# FreqRef.net
KiCad netlist of a schematic drawn in EAGLE
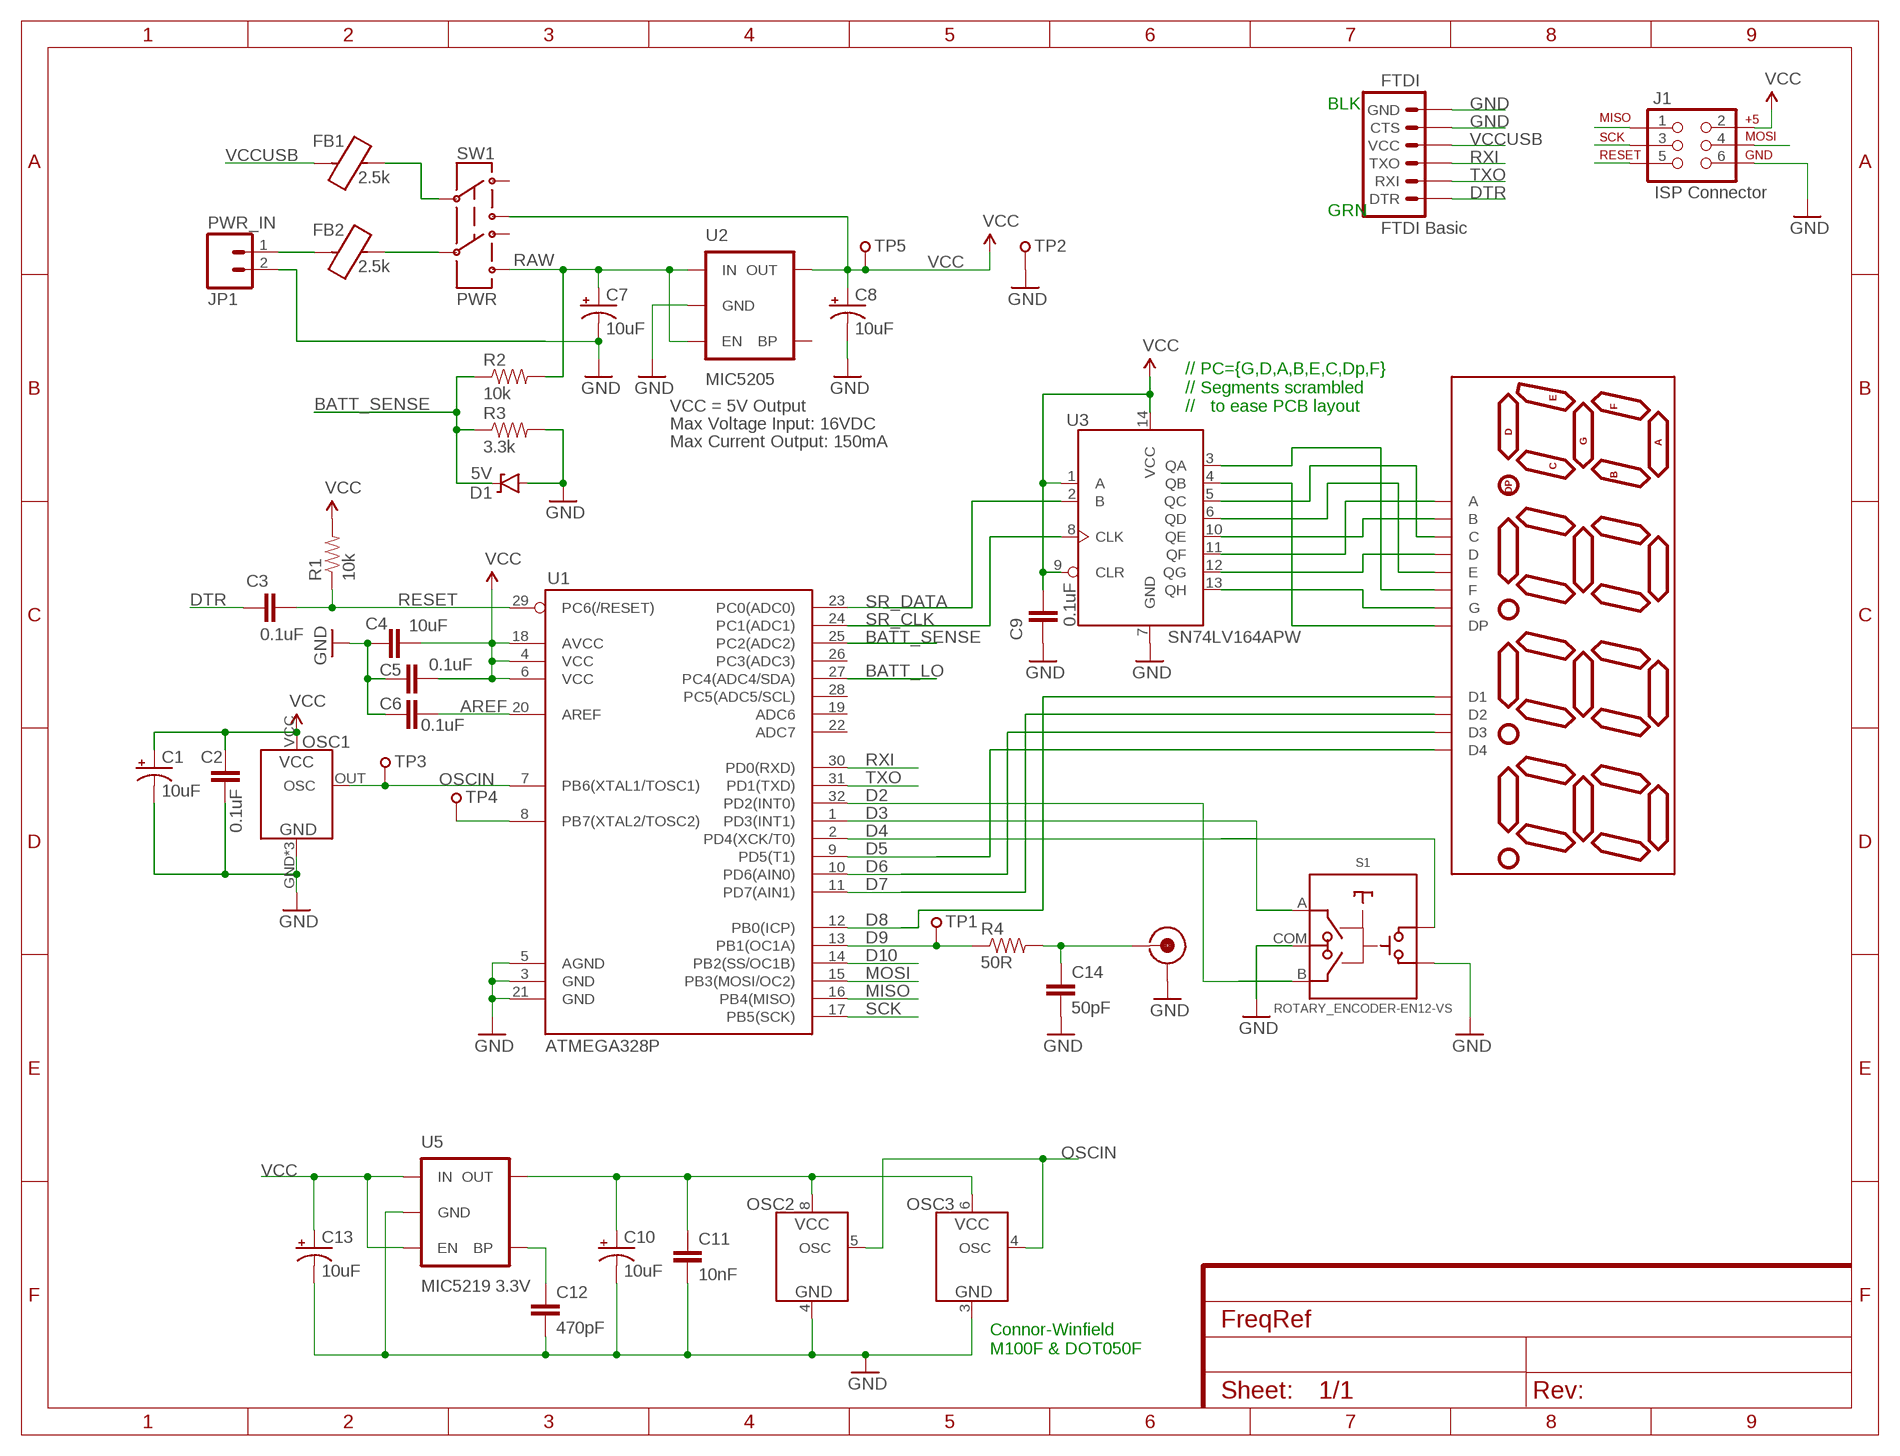
[diagram p0: schematic, sheet 1]

(export (version "E")
  (design (tool "Eeschema 10.0.6"))
  (components
    (comp (ref "C1")
      (value "10uF")
      (footprint "eagle-import:0805-POL")
      (libsource (lib "eagle-import") (part "CAP_POL0805"))
    )
    (comp (ref "C2")
      (value "0.1uF")
      (footprint "eagle-import:0805")
      (libsource (lib "eagle-import") (part "CAP0805"))
    )
    (comp (ref "C3")
      (value "0.1uF")
      (footprint "eagle-import:0805")
      (libsource (lib "eagle-import") (part "CAP0805"))
    )
    (comp (ref "C4")
      (value "10uF")
      (footprint "eagle-import:0805")
      (libsource (lib "eagle-import") (part "CAP0805"))
    )
    (comp (ref "C5")
      (value "0.1uF")
      (footprint "eagle-import:0805")
      (libsource (lib "eagle-import") (part "CAP0805"))
    )
    (comp (ref "C6")
      (value "0.1uF")
      (footprint "eagle-import:0805")
      (libsource (lib "eagle-import") (part "CAP0805"))
    )
    (comp (ref "C7")
      (value "10uF")
      (footprint "eagle-import:0805-POL")
      (libsource (lib "eagle-import") (part "CAP_POL0805"))
    )
    (comp (ref "C8")
      (value "10uF")
      (footprint "eagle-import:0805-POL")
      (libsource (lib "eagle-import") (part "CAP_POL0805"))
    )
    (comp (ref "C9")
      (value "0.1uF")
      (footprint "eagle-import:0805")
      (libsource (lib "eagle-import") (part "CAP0805"))
    )
    (comp (ref "C10")
      (value "10uF")
      (footprint "eagle-import:0805-POL")
      (libsource (lib "eagle-import") (part "CAP_POL0805"))
    )
    (comp (ref "C11")
      (value "10nF")
      (footprint "eagle-import:0805")
      (libsource (lib "eagle-import") (part "CAP0805"))
    )
    (comp (ref "C12")
      (value "470pF")
      (footprint "eagle-import:0805")
      (libsource (lib "eagle-import") (part "CAP0805"))
    )
    (comp (ref "C13")
      (value "10uF")
      (footprint "eagle-import:0805-POL")
      (libsource (lib "eagle-import") (part "CAP_POL0805"))
    )
    (comp (ref "C14")
      (value "50pF")
      (footprint "eagle-import:0805")
      (libsource (lib "eagle-import") (part "CAP0805"))
    )
    (comp (ref "D1")
      (value "5V")
      (footprint "eagle-import:SOD-323")
      (libsource (lib "eagle-import") (part "DIODE-ZENER3.3V"))
    )
    (comp (ref "DISP1")
      (value "HP_DISPLAY")
      (footprint "eagle-import:DIL12")
      (libsource (lib "eagle-import") (part "HP_DISPLAY"))
    )
    (comp (ref "FB1")
      (value "2.5k")
      (footprint "eagle-import:0805")
      (libsource (lib "eagle-import") (part "FERRITE_BEAD_0805"))
    )
    (comp (ref "FB2")
      (value "2.5k")
      (footprint "eagle-import:0805")
      (libsource (lib "eagle-import") (part "FERRITE_BEAD_0805"))
    )
    (comp (ref "FRAME1")
      (value "FRAME_LTR_CU_MARK")
      (footprint "eagle-import:FR-LTR-ON-PCB")
      (fields
        (field (name "CNAME") "Frequency Reference")
        (field (name "CREVISION") "Rev-B")
        (field (name "DESIGNER") "C.Schnarel")
      )
      (libsource (lib "eagle-import") (part "FRAME_LTR_CU_MARK"))
    )
    (comp (ref "FTDI")
      (value "FTDI Basic")
      (footprint "eagle-import:1X06")
      (libsource (lib "eagle-import") (part "ARDUINO_SERIAL_PROGRAMPTH"))
    )
    (comp (ref "J1")
      (value "ISP Connector")
      (footprint "eagle-import:2X3")
      (libsource (lib "eagle-import") (part "AVR_SPI_PRG_6PTH"))
    )
    (comp (ref "J2")
      (value "BNC_RIGHT-ANGLE")
      (footprint "eagle-import:BNC-RIGHT-ANGLE")
      (libsource (lib "eagle-import") (part "BNC_RIGHT-ANGLE"))
    )
    (comp (ref "JP1")
      (value "PWR_IN")
      (footprint "eagle-import:MOLEX-1X2")
      (libsource (lib "eagle-import") (part "M02POLAR"))
    )
    (comp (ref "OSC1")
      (value "TCXORALTRON")
      (footprint "eagle-import:TCXO")
      (libsource (lib "eagle-import") (part "TCXORALTRON"))
    )
    (comp (ref "OSC2")
      (value "TCXOM100")
      (footprint "eagle-import:TCXO-3.2X5")
      (libsource (lib "eagle-import") (part "TCXOM100"))
    )
    (comp (ref "OSC3")
      (value "TCXODOT")
      (footprint "eagle-import:TCXO-9X14")
      (libsource (lib "eagle-import") (part "TCXODOT"))
    )
    (comp (ref "R1")
      (value "10k")
      (footprint "eagle-import:0805")
      (libsource (lib "eagle-import") (part "RESISTOR0805-RES"))
    )
    (comp (ref "R2")
      (value "10k")
      (footprint "eagle-import:0805")
      (libsource (lib "eagle-import") (part "RESISTOR0805-RES"))
    )
    (comp (ref "R3")
      (value "3.3k")
      (footprint "eagle-import:0805")
      (libsource (lib "eagle-import") (part "RESISTOR0805-RES"))
    )
    (comp (ref "R4")
      (value "50R")
      (footprint "eagle-import:0805")
      (libsource (lib "eagle-import") (part "RESISTOR0805-RES"))
    )
    (comp (ref "S1")
      (value "ROTARY_ENCODER-EN12-VS")
      (footprint "eagle-import:EN12-VS")
      (libsource (lib "eagle-import") (part "ROTARY_ENCODER-EN12-VS"))
    )
    (comp (ref "SW1")
      (value "PWR")
      (footprint "eagle-import:8X10_BUTTON_ROUND")
      (libsource (lib "eagle-import") (part "SWITCH,BUTTON,ROUND,7MM"))
    )
    (comp (ref "TP1")
      (value "TEST_POINT")
      (footprint "eagle-import:BBD-VIA")
      (libsource (lib "eagle-import") (part "TEST_POINT"))
    )
    (comp (ref "TP2")
      (value "TEST_POINT")
      (footprint "eagle-import:BBD-VIA")
      (libsource (lib "eagle-import") (part "TEST_POINT"))
    )
    (comp (ref "TP3")
      (value "TEST_POINT")
      (footprint "eagle-import:BBD-VIA")
      (libsource (lib "eagle-import") (part "TEST_POINT"))
    )
    (comp (ref "TP4")
      (value "TEST_POINT")
      (footprint "eagle-import:BBD-VIA")
      (libsource (lib "eagle-import") (part "TEST_POINT"))
    )
    (comp (ref "TP5")
      (value "TEST_POINT")
      (footprint "eagle-import:BBD-VIA")
      (libsource (lib "eagle-import") (part "TEST_POINT"))
    )
    (comp (ref "U1")
      (value "ATMEGA328P")
      (footprint "eagle-import:TQFP32-08")
      (libsource (lib "eagle-import") (part "ATMEGA168"))
    )
    (comp (ref "U2")
      (value "MIC5205")
      (footprint "eagle-import:SOT23-5")
      (libsource (lib "eagle-import") (part "V_REG_LDOSMD"))
    )
    (comp (ref "U3")
      (value "SN74LV164APW")
      (footprint "eagle-import:TSSOP-14(TI)")
      (libsource (lib "eagle-import") (part "SN74LV164APW"))
    )
    (comp (ref "U5")
      (value "MIC5219 3.3V")
      (footprint "eagle-import:SOT23-5")
      (libsource (lib "eagle-import") (part "V_REG_MIC52193.3V"))
    )
  )
  (nets
    (net (code "1") (name "/AREF") (class "Default")
      (node (ref "C6") (pin "2") (pinfunction "2_2") (pintype "passive"))
      (node (ref "U1") (pin "20") (pinfunction "AREF_20") (pintype "bidirectional"))
    )
    (net (code "2") (name "/BATT_LO") (class "Default")
      (node (ref "U1") (pin "27") (pinfunction "PC4(ADC4/SDA)_27") (pintype "bidirectional"))
    )
    (net (code "3") (name "/BATT_SENSE") (class "Default")
      (node (ref "D1") (pin "C") (pinfunction "C_C") (pintype "passive"))
      (node (ref "R2") (pin "1") (pinfunction "1_1") (pintype "passive"))
      (node (ref "R3") (pin "1") (pinfunction "1_1") (pintype "passive"))
      (node (ref "U1") (pin "25") (pinfunction "PC2(ADC2)_25") (pintype "bidirectional"))
    )
    (net (code "4") (name "/D2") (class "Default")
      (node (ref "S1") (pin "B") (pinfunction "B_B") (pintype "bidirectional"))
      (node (ref "U1") (pin "32") (pinfunction "PD2(INT0)_32") (pintype "bidirectional"))
    )
    (net (code "5") (name "/D3") (class "Default")
      (node (ref "S1") (pin "A") (pinfunction "A_A") (pintype "bidirectional"))
      (node (ref "U1") (pin "1") (pinfunction "PD3(INT1)_1") (pintype "bidirectional"))
    )
    (net (code "6") (name "/D4") (class "Default")
      (node (ref "S1") (pin "D") (pinfunction "P$4_D") (pintype "bidirectional"))
      (node (ref "U1") (pin "2") (pinfunction "PD4(XCK/T0)_2") (pintype "bidirectional"))
    )
    (net (code "7") (name "/D5") (class "Default")
      (node (ref "DISP1") (pin "6") (pinfunction "D4_6") (pintype "bidirectional"))
      (node (ref "U1") (pin "9") (pinfunction "PD5(T1)_9") (pintype "bidirectional"))
    )
    (net (code "8") (name "/D6") (class "Default")
      (node (ref "DISP1") (pin "4") (pinfunction "D3_4") (pintype "bidirectional"))
      (node (ref "U1") (pin "10") (pinfunction "PD6(AIN0)_10") (pintype "bidirectional"))
    )
    (net (code "9") (name "/D7") (class "Default")
      (node (ref "DISP1") (pin "10") (pinfunction "D2_10") (pintype "bidirectional"))
      (node (ref "U1") (pin "11") (pinfunction "PD7(AIN1)_11") (pintype "bidirectional"))
    )
    (net (code "10") (name "/D8") (class "Default")
      (node (ref "DISP1") (pin "1") (pinfunction "D1_1") (pintype "bidirectional"))
      (node (ref "U1") (pin "12") (pinfunction "PB0(ICP)_12") (pintype "bidirectional"))
    )
    (net (code "11") (name "/D9") (class "Default")
      (node (ref "R4") (pin "1") (pinfunction "1_1") (pintype "passive"))
      (node (ref "TP1") (pin "P$1") (pinfunction "P$1_P$1") (pintype "bidirectional"))
      (node (ref "U1") (pin "13") (pinfunction "PB1(OC1A)_13") (pintype "bidirectional"))
    )
    (net (code "12") (name "/D10") (class "Default")
      (node (ref "U1") (pin "14") (pinfunction "PB2(SS/OC1B)_14") (pintype "bidirectional"))
    )
    (net (code "13") (name "/DTR") (class "Default")
      (node (ref "C3") (pin "1") (pinfunction "1_1") (pintype "passive"))
      (node (ref "FTDI") (pin "1") (pinfunction "DTR_1") (pintype "passive"))
    )
    (net (code "14") (name "/MISO") (class "Default")
      (node (ref "J1") (pin "1") (pinfunction "1_1") (pintype "passive"))
      (node (ref "U1") (pin "16") (pinfunction "PB4(MISO)_16") (pintype "bidirectional"))
    )
    (net (code "15") (name "/MOSI") (class "Default")
      (node (ref "J1") (pin "4") (pinfunction "4_4") (pintype "passive"))
      (node (ref "U1") (pin "15") (pinfunction "PB3(MOSI/OC2)_15") (pintype "bidirectional"))
    )
    (net (code "16") (name "/OSCIN") (class "Default")
      (node (ref "OSC1") (pin "OUT") (pinfunction "OSC_OUT") (pintype "bidirectional"))
      (node (ref "OSC2") (pin "5") (pinfunction "OSC_5") (pintype "bidirectional"))
      (node (ref "OSC3") (pin "4") (pinfunction "OSC_4") (pintype "bidirectional"))
      (node (ref "TP3") (pin "P$1") (pinfunction "P$1_P$1") (pintype "bidirectional"))
      (node (ref "U1") (pin "7") (pinfunction "PB6(XTAL1/TOSC1)_7") (pintype "bidirectional"))
    )
    (net (code "17") (name "/RAW") (class "Default")
      (node (ref "C7") (pin "1") (pinfunction "+_1") (pintype "passive"))
      (node (ref "R2") (pin "2") (pinfunction "2_2") (pintype "passive"))
      (node (ref "SW1") (pin "2NO") (pinfunction "2NO_2NO") (pintype "bidirectional"))
      (node (ref "U2") (pin "1") (pinfunction "IN_1") (pintype "input"))
      (node (ref "U2") (pin "3") (pinfunction "EN_3") (pintype "input"))
    )
    (net (code "18") (name "/RESET") (class "Default")
      (node (ref "C3") (pin "2") (pinfunction "2_2") (pintype "passive"))
      (node (ref "J1") (pin "5") (pinfunction "5_5") (pintype "passive"))
      (node (ref "R1") (pin "1") (pinfunction "1_1") (pintype "passive"))
      (node (ref "U1") (pin "29") (pinfunction "PC6(/RESET)_29") (pintype "bidirectional"))
    )
    (net (code "19") (name "/RXI") (class "Default")
      (node (ref "FTDI") (pin "3") (pinfunction "TXO_3") (pintype "passive"))
      (node (ref "U1") (pin "30") (pinfunction "PD0(RXD)_30") (pintype "bidirectional"))
    )
    (net (code "20") (name "/SCK") (class "Default")
      (node (ref "J1") (pin "3") (pinfunction "3_3") (pintype "passive"))
      (node (ref "U1") (pin "17") (pinfunction "PB5(SCK)_17") (pintype "bidirectional"))
    )
    (net (code "21") (name "/SR_CLK") (class "Default")
      (node (ref "U1") (pin "24") (pinfunction "PC1(ADC1)_24") (pintype "bidirectional"))
      (node (ref "U3") (pin "8") (pinfunction "CLK_8") (pintype "input"))
    )
    (net (code "22") (name "/SR_DATA") (class "Default")
      (node (ref "U1") (pin "23") (pinfunction "PC0(ADC0)_23") (pintype "bidirectional"))
      (node (ref "U3") (pin "2") (pinfunction "B_2") (pintype "input"))
    )
    (net (code "23") (name "/TXO") (class "Default")
      (node (ref "FTDI") (pin "2") (pinfunction "RXI_2") (pintype "passive"))
      (node (ref "U1") (pin "31") (pinfunction "PD1(TXD)_31") (pintype "bidirectional"))
    )
    (net (code "24") (name "/VCCUSB") (class "Default")
      (node (ref "FB1") (pin "1") (pinfunction "1_1") (pintype "passive"))
      (node (ref "FTDI") (pin "4") (pinfunction "VCC_4") (pintype "passive"))
    )
    (net (code "25") (name "GND") (class "Default")
      (node (ref "C1") (pin "2") (pinfunction "-_2") (pintype "passive"))
      (node (ref "C10") (pin "2") (pinfunction "-_2") (pintype "passive"))
      (node (ref "C11") (pin "2") (pinfunction "2_2") (pintype "passive"))
      (node (ref "C12") (pin "2") (pinfunction "2_2") (pintype "passive"))
      (node (ref "C13") (pin "2") (pinfunction "-_2") (pintype "passive"))
      (node (ref "C14") (pin "2") (pinfunction "2_2") (pintype "passive"))
      (node (ref "C2") (pin "1") (pinfunction "1_1") (pintype "passive"))
      (node (ref "C4") (pin "1") (pinfunction "1_1") (pintype "passive"))
      (node (ref "C5") (pin "1") (pinfunction "1_1") (pintype "passive"))
      (node (ref "C6") (pin "1") (pinfunction "1_1") (pintype "passive"))
      (node (ref "C7") (pin "2") (pinfunction "-_2") (pintype "passive"))
      (node (ref "C8") (pin "2") (pinfunction "-_2") (pintype "passive"))
      (node (ref "C9") (pin "1") (pinfunction "1_1") (pintype "passive"))
      (node (ref "D1") (pin "A") (pinfunction "A_A") (pintype "passive"))
      (node (ref "FTDI") (pin "5") (pinfunction "CTS_5") (pintype "passive"))
      (node (ref "FTDI") (pin "6") (pinfunction "GND_6") (pintype "passive"))
      (node (ref "J1") (pin "6") (pinfunction "6_6") (pintype "passive"))
      (node (ref "J2") (pin "SHD") (pinfunction "SHD_SHD") (pintype "bidirectional"))
      (node (ref "JP1") (pin "2") (pinfunction "2_2") (pintype "passive"))
      (node (ref "OSC1") (pin "GND") (pinfunction "GND_GND") (pintype "bidirectional"))
      (node (ref "OSC1") (pin "SHLD1") (pinfunction "GND_SHLD1") (pintype "bidirectional"))
      (node (ref "OSC1") (pin "SHLD2") (pinfunction "GND_SHLD2") (pintype "bidirectional"))
      (node (ref "OSC2") (pin "4") (pinfunction "GND_4") (pintype "bidirectional"))
      (node (ref "OSC3") (pin "3") (pinfunction "GND_3") (pintype "bidirectional"))
      (node (ref "R3") (pin "2") (pinfunction "2_2") (pintype "passive"))
      (node (ref "S1") (pin "COM") (pinfunction "COM_COM") (pintype "bidirectional"))
      (node (ref "S1") (pin "E") (pinfunction "P$5_E") (pintype "bidirectional"))
      (node (ref "TP2") (pin "P$1") (pinfunction "P$1_P$1") (pintype "bidirectional"))
      (node (ref "U1") (pin "21") (pinfunction "GND_21") (pintype "bidirectional"))
      (node (ref "U1") (pin "3") (pinfunction "GND_3") (pintype "bidirectional"))
      (node (ref "U1") (pin "5") (pinfunction "AGND_5") (pintype "bidirectional"))
      (node (ref "U2") (pin "2") (pinfunction "GND_2") (pintype "input"))
      (node (ref "U3") (pin "7") (pinfunction "GND_7") (pintype "power_in"))
      (node (ref "U5") (pin "2") (pinfunction "GND_2") (pintype "input"))
    )
    (net (code "26") (name "Net-(C10-+)") (class "Default")
      (node (ref "C10") (pin "1") (pinfunction "+_1") (pintype "passive"))
      (node (ref "C11") (pin "1") (pinfunction "1_1") (pintype "passive"))
      (node (ref "OSC2") (pin "8") (pinfunction "VCC_8") (pintype "bidirectional"))
      (node (ref "OSC3") (pin "6") (pinfunction "VCC_6") (pintype "bidirectional"))
      (node (ref "U5") (pin "5") (pinfunction "OUT_5") (pintype "passive"))
    )
    (net (code "27") (name "Net-(C14-Pad1)") (class "Default")
      (node (ref "C14") (pin "1") (pinfunction "1_1") (pintype "passive"))
      (node (ref "J2") (pin "CTR") (pinfunction "CTR_CTR") (pintype "bidirectional"))
      (node (ref "R4") (pin "2") (pinfunction "2_2") (pintype "passive"))
    )
    (net (code "28") (name "Net-(DISP1-A)") (class "Default")
      (node (ref "DISP1") (pin "12") (pinfunction "A_12") (pintype "bidirectional"))
      (node (ref "U3") (pin "11") (pinfunction "QF_11") (pintype "bidirectional"))
    )
    (net (code "29") (name "Net-(DISP1-B)") (class "Default")
      (node (ref "DISP1") (pin "11") (pinfunction "B_11") (pintype "bidirectional"))
      (node (ref "U3") (pin "10") (pinfunction "QE_10") (pintype "bidirectional"))
    )
    (net (code "30") (name "Net-(DISP1-C)") (class "Default")
      (node (ref "DISP1") (pin "3") (pinfunction "C_3") (pintype "bidirectional"))
      (node (ref "U3") (pin "5") (pinfunction "QC_5") (pintype "bidirectional"))
    )
    (net (code "31") (name "Net-(DISP1-D)") (class "Default")
      (node (ref "DISP1") (pin "8") (pinfunction "D_8") (pintype "bidirectional"))
      (node (ref "U3") (pin "12") (pinfunction "QG_12") (pintype "bidirectional"))
    )
    (net (code "32") (name "Net-(DISP1-DP)") (class "Default")
      (node (ref "DISP1") (pin "5") (pinfunction "DP_5") (pintype "bidirectional"))
      (node (ref "U3") (pin "4") (pinfunction "QB_4") (pintype "bidirectional"))
    )
    (net (code "33") (name "Net-(DISP1-E)") (class "Default")
      (node (ref "DISP1") (pin "2") (pinfunction "E_2") (pintype "bidirectional"))
      (node (ref "U3") (pin "6") (pinfunction "QD_6") (pintype "bidirectional"))
    )
    (net (code "34") (name "Net-(DISP1-F)") (class "Default")
      (node (ref "DISP1") (pin "9") (pinfunction "F_9") (pintype "bidirectional"))
      (node (ref "U3") (pin "3") (pinfunction "QA_3") (pintype "bidirectional"))
    )
    (net (code "35") (name "Net-(DISP1-G)") (class "Default")
      (node (ref "DISP1") (pin "7") (pinfunction "G_7") (pintype "bidirectional"))
      (node (ref "U3") (pin "13") (pinfunction "QH_13") (pintype "bidirectional"))
    )
    (net (code "36") (name "Net-(FB1-Pad2)") (class "Default")
      (node (ref "FB1") (pin "2") (pinfunction "2_2") (pintype "passive"))
      (node (ref "SW1") (pin "1C") (pinfunction "1C_1C") (pintype "bidirectional"))
    )
    (net (code "37") (name "Net-(FB2-Pad1)") (class "Default")
      (node (ref "FB2") (pin "1") (pinfunction "1_1") (pintype "passive"))
      (node (ref "JP1") (pin "1") (pinfunction "1_1") (pintype "passive"))
    )
    (net (code "38") (name "Net-(FB2-Pad2)") (class "Default")
      (node (ref "FB2") (pin "2") (pinfunction "2_2") (pintype "passive"))
      (node (ref "SW1") (pin "2C") (pinfunction "2C_2C") (pintype "bidirectional"))
    )
    (net (code "39") (name "Net-(U1-PB7(XTAL2{slash}TOSC2))") (class "Default")
      (node (ref "TP4") (pin "P$1") (pinfunction "P$1_P$1") (pintype "bidirectional"))
      (node (ref "U1") (pin "8") (pinfunction "PB7(XTAL2/TOSC2)_8") (pintype "bidirectional"))
    )
    (net (code "40") (name "Net-(U5-BP)") (class "Default")
      (node (ref "C12") (pin "1") (pinfunction "1_1") (pintype "passive"))
      (node (ref "U5") (pin "4") (pinfunction "BP_4") (pintype "input"))
    )
    (net (code "41") (name "VCC") (class "Default")
      (node (ref "C1") (pin "1") (pinfunction "+_1") (pintype "passive"))
      (node (ref "C13") (pin "1") (pinfunction "+_1") (pintype "passive"))
      (node (ref "C2") (pin "2") (pinfunction "2_2") (pintype "passive"))
      (node (ref "C4") (pin "2") (pinfunction "2_2") (pintype "passive"))
      (node (ref "C5") (pin "2") (pinfunction "2_2") (pintype "passive"))
      (node (ref "C8") (pin "1") (pinfunction "+_1") (pintype "passive"))
      (node (ref "C9") (pin "2") (pinfunction "2_2") (pintype "passive"))
      (node (ref "J1") (pin "2") (pinfunction "2_2") (pintype "passive"))
      (node (ref "OSC1") (pin "VCC") (pinfunction "VCC_VCC") (pintype "bidirectional"))
      (node (ref "R1") (pin "2") (pinfunction "2_2") (pintype "passive"))
      (node (ref "SW1") (pin "1NO") (pinfunction "1NO_1NO") (pintype "bidirectional"))
      (node (ref "TP5") (pin "P$1") (pinfunction "P$1_P$1") (pintype "bidirectional"))
      (node (ref "U1") (pin "18") (pinfunction "AVCC_18") (pintype "bidirectional"))
      (node (ref "U1") (pin "4") (pinfunction "VCC_4") (pintype "bidirectional"))
      (node (ref "U1") (pin "6") (pinfunction "VCC_6") (pintype "bidirectional"))
      (node (ref "U2") (pin "5") (pinfunction "OUT_5") (pintype "passive"))
      (node (ref "U3") (pin "1") (pinfunction "A_1") (pintype "bidirectional"))
      (node (ref "U3") (pin "14") (pinfunction "VCC_14") (pintype "power_in"))
      (node (ref "U3") (pin "9") (pinfunction "CLR_9") (pintype "bidirectional"))
      (node (ref "U5") (pin "1") (pinfunction "IN_1") (pintype "input"))
      (node (ref "U5") (pin "3") (pinfunction "EN_3") (pintype "input"))
    )
    (net (code "42") (name "unconnected-(SW1-Pad1NC)") (class "Default")
      (node (ref "SW1") (pin "1NC") (pinfunction "1NC_1NC") (pintype "bidirectional"))
    )
    (net (code "43") (name "unconnected-(SW1-Pad2NC)") (class "Default")
      (node (ref "SW1") (pin "2NC") (pinfunction "2NC_2NC") (pintype "bidirectional"))
    )
    (net (code "44") (name "unconnected-(U1-ADC6-Pad19)") (class "Default")
      (node (ref "U1") (pin "19") (pinfunction "ADC6_19") (pintype "bidirectional"))
    )
    (net (code "45") (name "unconnected-(U1-ADC7-Pad22)") (class "Default")
      (node (ref "U1") (pin "22") (pinfunction "ADC7_22") (pintype "bidirectional"))
    )
    (net (code "46") (name "unconnected-(U1-PC3(ADC3)-Pad26)") (class "Default")
      (node (ref "U1") (pin "26") (pinfunction "PC3(ADC3)_26") (pintype "bidirectional"))
    )
    (net (code "47") (name "unconnected-(U1-PC5(ADC5{slash}SCL)-Pad28)") (class "Default")
      (node (ref "U1") (pin "28") (pinfunction "PC5(ADC5/SCL)_28") (pintype "bidirectional"))
    )
    (net (code "48") (name "unconnected-(U2-BP-Pad4)") (class "Default")
      (node (ref "U2") (pin "4") (pinfunction "BP_4") (pintype "input"))
    )
  )
)
